# Solenoid.net
KiCad netlist of a schematic drawn in Altium Designer
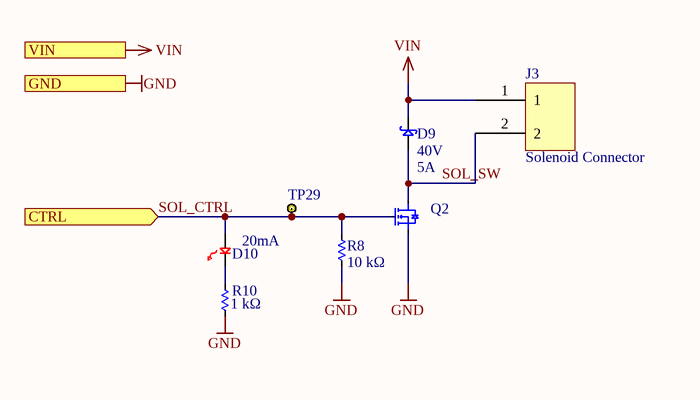
[diagram p0: Solenoid.SchDoc]

(export (version "E")
  (design (tool "Eeschema 10.0.6"))
  (components
    (comp (ref "D9")
      (value "SCHOTTKY_B540C-13-F")
      (footprint "SMC")
      (description "DIODE SCHOTTKY 40V 5A SMC")
      (fields
        (field (name "MANUFACTURER") "Diodes Inc")
        (field (name "MANUFACTURER PART NUMBER") "B540C-13-F")
        (field (name "VOLTAGE - DC REVERSE (VR) (MAX)") "40V")
        (field (name "CURRENT - AVERAGE RECTIFIED (IO)") "5A")
      )
      (libsource (lib "Stanford Student Space Initiative") (part "Symbol"))
    )
    (comp (ref "D10")
      (value "LED_LY974")
      (footprint "0805_Diode")
      (description "LED 0805 RED 20MA")
      (fields
        (field (name "MANUFACTURER") "OSRAM Opto Semiconductors Inc")
        (field (name "MANUFACTURER PART NUMBER") "LH R974-LP-1")
        (field (name "CURRENT - TEST") "20mA")
      )
      (libsource (lib "Stanford Student Space Initiative") (part "LED_LY974"))
    )
    (comp (ref "J3")
      (value "Solenoid Connector")
      (footprint "Molex 172310-xx02")
      (description "ULTRAFIT CONN HEADER R/A 2POS 3.5MM")
      (libsource (lib "Stanford Student Space Initiative") (part "MOLEX_1x2_1723101102"))
    )
    (comp (ref "Q2")
      (value "NFET_CSD16323Q3")
      (footprint "8-VSON-THERMALS")
      (description "MOSFET N-CH 25V 3.3X3.3 8-SON")
      (fields
        (field (name "MANUFACTURER PART NUMBER") "CSD16323Q3")
        (field (name "MANUFACTURER") "Texas Instruments")
      )
      (libsource (lib "Stanford Student Space Initiative") (part "NFET"))
    )
    (comp (ref "R8")
      (value "311-10.0KHRCT-ND")
      (footprint "R0603")
      (description "RES SMD 10K OHM 1% 1/10W 0603")
      (fields
        (field (name "RESISTANCE") "10 kΩ")
        (field (name "MANUFACTURER PART NUMBER") "RC0603FR-0710KL")
        (field (name "MANUFACTURER") "Yageo")
      )
      (libsource (lib "Stanford Student Space Initiative") (part "__template_resistor"))
    )
    (comp (ref "R10")
      (value "311-1.00KHRCT-ND")
      (footprint "R0603")
      (description "RES SMD 1K OHM 1% 1/10W 0603")
      (fields
        (field (name "MANUFACTURER") "Yageo")
        (field (name "TOLERANCE") "±1%")
        (field (name "RESISTANCE") "1 kΩ")
      )
      (libsource (lib "Stanford Student Space Initiative") (part "__template_resistor"))
    )
    (comp (ref "TP29")
      (value "TEST_POINT_BLACK_KEYSTONE_5001")
      (footprint "TEST_POINT_KEYSTONE_5001")
      (description "BLACK T/H TEST POINT")
      (fields
        (field (name "MANUFACTURER PART NUMBER") "5001")
        (field (name "MANUFACTURER") "Keystone Electronics")
      )
      (libsource (lib "Stanford Student Space Initiative") (part "TEST_POINT_BLACK_KEYSTONE_5001"))
    )
  )
  (nets
    (net (code "1") (name "/SOL_CTRL") (class "Default")
      (node (ref "D10") (pin "2") (pintype "passive"))
      (node (ref "Q2") (pin "2") (pinfunction "G_2") (pintype "passive"))
      (node (ref "R8") (pin "2") (pinfunction "2_2") (pintype "passive"))
      (node (ref "TP29") (pin "1") (pinfunction "1_1") (pintype "passive"))
    )
    (net (code "2") (name "/SOL_SW") (class "Default")
      (node (ref "D9") (pin "1") (pintype "passive"))
      (node (ref "J3") (pin "2") (pinfunction "2_2") (pintype "passive"))
      (node (ref "Q2") (pin "1") (pinfunction "D_1") (pintype "passive"))
    )
    (net (code "3") (name "GND") (class "Default")
      (node (ref "Q2") (pin "3") (pinfunction "S_3") (pintype "passive"))
      (node (ref "R10") (pin "1") (pinfunction "1_1") (pintype "passive"))
      (node (ref "R8") (pin "1") (pinfunction "1_1") (pintype "passive"))
    )
    (net (code "4") (name "Net-(D10-Pad1)") (class "Default")
      (node (ref "D10") (pin "1") (pintype "passive"))
      (node (ref "R10") (pin "2") (pinfunction "2_2") (pintype "passive"))
    )
    (net (code "5") (name "VIN") (class "Default")
      (node (ref "D9") (pin "2") (pintype "passive"))
      (node (ref "J3") (pin "1") (pinfunction "1_1") (pintype "passive"))
    )
  )
)
